# CH3-Isolation.net
KiCad netlist of a schematic drawn in Altium Designer
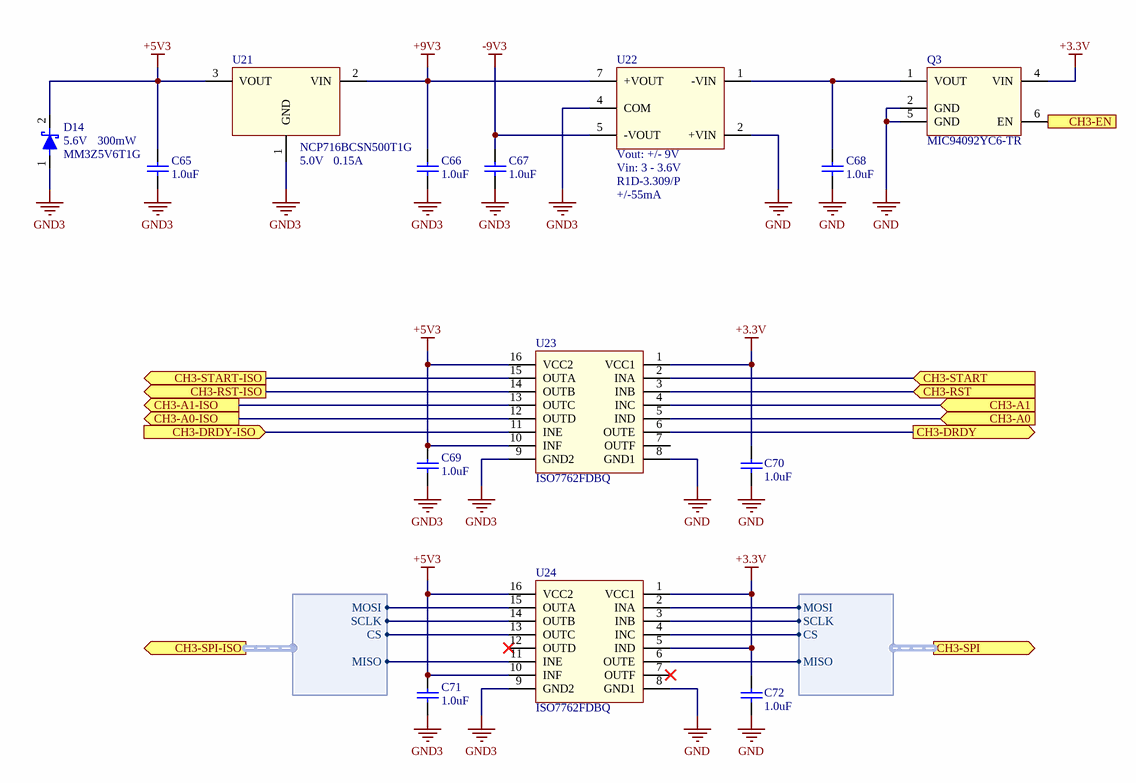
[diagram p0: CH3-Isolation.SchDoc]

(export (version "E")
  (design (tool "Eeschema 10.0.6"))
  (components
    (comp (ref "C65")
      (value "1.0uF")
      (footprint "CAP-0603")
      (description "CAP CER 1uF 25V X7R 0603")
      (fields (field (name "PARTNUMBER") "C0603C105M3RAC7867") (field (name "MANUFACTURER") "Kemet"))
      (libsource (lib "Kemet") (part "C0603C105M3RAC7867"))
    )
    (comp (ref "C66")
      (value "1.0uF")
      (footprint "CAP-0603")
      (description "CAP CER 1uF 25V X7R 0603")
      (fields (field (name "PARTNUMBER") "C0603C105M3RAC7867") (field (name "MANUFACTURER") "Kemet"))
      (libsource (lib "Kemet") (part "C0603C105M3RAC7867"))
    )
    (comp (ref "C67")
      (value "1.0uF")
      (footprint "CAP-0603")
      (description "CAP CER 1uF 25V X7R 0603")
      (fields (field (name "PARTNUMBER") "C0603C105M3RAC7867") (field (name "MANUFACTURER") "Kemet"))
      (libsource (lib "Kemet") (part "C0603C105M3RAC7867"))
    )
    (comp (ref "C68")
      (value "1.0uF")
      (footprint "CAP-0603")
      (description "CAP CER 1uF 25V X7R 0603")
      (fields (field (name "PARTNUMBER") "C0603C105M3RAC7867") (field (name "MANUFACTURER") "Kemet"))
      (libsource (lib "Kemet") (part "C0603C105M3RAC7867"))
    )
    (comp (ref "C69")
      (value "1.0uF")
      (footprint "CAP-0603")
      (description "CAP CER 1uF 25V X7R 0603")
      (fields (field (name "PARTNUMBER") "C0603C105M3RAC7867") (field (name "MANUFACTURER") "Kemet"))
      (libsource (lib "Kemet") (part "C0603C105M3RAC7867"))
    )
    (comp (ref "C70")
      (value "1.0uF")
      (footprint "CAP-0603")
      (description "CAP CER 1uF 25V X7R 0603")
      (fields (field (name "PARTNUMBER") "C0603C105M3RAC7867") (field (name "MANUFACTURER") "Kemet"))
      (libsource (lib "Kemet") (part "C0603C105M3RAC7867"))
    )
    (comp (ref "C71")
      (value "1.0uF")
      (footprint "CAP-0603")
      (description "CAP CER 1uF 25V X7R 0603")
      (fields (field (name "PARTNUMBER") "C0603C105M3RAC7867") (field (name "MANUFACTURER") "Kemet"))
      (libsource (lib "Kemet") (part "C0603C105M3RAC7867"))
    )
    (comp (ref "C72")
      (value "1.0uF")
      (footprint "CAP-0603")
      (description "CAP CER 1uF 25V X7R 0603")
      (fields (field (name "PARTNUMBER") "C0603C105M3RAC7867") (field (name "MANUFACTURER") "Kemet"))
      (libsource (lib "Kemet") (part "C0603C105M3RAC7867"))
    )
    (comp (ref "D14")
      (value "MM3Z5V6T1G")
      (footprint "SOD323 - DIODE UNIDIR")
      (description "Schottky Diode 30V 200mA SOT323")
      (fields
        (field (name "MANUFACTURER") "OnSemiconductor")
        (field (name "POWER") "300mW")
        (field (name "VZ") "5.6V")
        (field (name "PARTNUMBER") "MM3Z5V6T1G")
      )
      (libsource (lib "OnSemiconductors") (part "MM3Z5V6T1G"))
    )
    (comp (ref "Q3")
      (value "MIC94092YC6-TR")
      (footprint "TSSOP6")
      (fields (field (name "MANUFACTURER") "Microchip") (field (name "PARTNUMBER") "MIC94092YC6-TR"))
      (libsource (lib "Microchip") (part "MIC94092YC6-TR"))
    )
    (comp (ref "U21")
      (value "NCP716BCSN500T1G")
      (footprint "SOT23-5")
      (description "IC REG LDO 0.5V 0.15A TSOT23-5")
      (fields
        (field (name "MANUFACTURER") "ON Semiconductor")
        (field (name "PARTNUMBER") "NCP716BCSN500T1G")
        (field (name "VOLTAGE") "5.0V")
        (field (name "CURRENT") "0.15A")
      )
      (libsource (lib "OnSemiconductors") (part "NCP716BCSN500T1G"))
    )
    (comp (ref "U22")
      (value "R1D-3.309/P")
      (footprint "RECOM-R1D")
      (description "DC DC CONVERTER +/-9V 1W")
      (fields
        (field (name "MANUFACTURER") "Recom")
        (field (name "VOUT") "+/- 9V")
        (field (name "VIN") "3 - 3.6V")
        (field (name "PART NUMBER") "R1D-3.309/P")
        (field (name "CURRENT") "+/-55mA")
      )
      (libsource (lib "Recom") (part "R1D-3.309/P"))
    )
    (comp (ref "U23")
      (value "ISO7762FDBQ")
      (footprint "SSOP16")
      (description "Digital Isolator, six-channel, 4/2, 16-SSOP")
      (fields (field (name "MANUFACTURER") "Texas Instruments") (field (name "PARTNUMBER") "ISO7762FDBQ"))
      (libsource (lib "TexasInstruments") (part "ISO7762FDBQ"))
    )
    (comp (ref "U24")
      (value "ISO7762FDBQ")
      (footprint "SSOP16")
      (description "Digital Isolator, six-channel, 4/2, 16-SSOP")
      (fields (field (name "MANUFACTURER") "Texas Instruments") (field (name "PARTNUMBER") "ISO7762FDBQ"))
      (libsource (lib "TexasInstruments") (part "ISO7762FDBQ"))
    )
  )
  (nets
    (net (code "3") (name "+3.3V") (class "Default")
      (node (ref "C70") (pin "2") (pinfunction "2_2") (pintype "passive"))
      (node (ref "C72") (pin "2") (pinfunction "2_2") (pintype "passive"))
      (node (ref "Q3") (pin "4") (pinfunction "VIN_4") (pintype "passive"))
      (node (ref "U23") (pin "1") (pinfunction "VCC1_1") (pintype "passive"))
      (node (ref "U24") (pin "1") (pinfunction "VCC1_1") (pintype "passive"))
      (node (ref "U24") (pin "5") (pinfunction "IND_5") (pintype "passive"))
    )
    (net (code "4") (name "+5V3") (class "Default")
      (node (ref "C65") (pin "2") (pinfunction "2_2") (pintype "passive"))
      (node (ref "C69") (pin "2") (pinfunction "2_2") (pintype "passive"))
      (node (ref "C71") (pin "2") (pinfunction "2_2") (pintype "passive"))
      (node (ref "D14") (pin "2") (pinfunction "K_2") (pintype "passive"))
      (node (ref "U21") (pin "3") (pinfunction "VOUT_3") (pintype "passive"))
      (node (ref "U23") (pin "10") (pinfunction "INF_10") (pintype "passive"))
      (node (ref "U23") (pin "16") (pinfunction "VCC2_16") (pintype "passive"))
      (node (ref "U24") (pin "10") (pinfunction "INF_10") (pintype "passive"))
      (node (ref "U24") (pin "16") (pinfunction "VCC2_16") (pintype "passive"))
    )
    (net (code "5") (name "+9V3") (class "Default")
      (node (ref "C66") (pin "2") (pinfunction "2_2") (pintype "passive"))
      (node (ref "U21") (pin "2") (pinfunction "VIN_2") (pintype "passive"))
      (node (ref "U22") (pin "7") (pinfunction "+VOUT_7") (pintype "passive"))
    )
    (net (code "6") (name "-9V3") (class "Default")
      (node (ref "C67") (pin "2") (pinfunction "2_2") (pintype "passive"))
      (node (ref "U22") (pin "5") (pinfunction "-VOUT_5") (pintype "passive"))
    )
    (net (code "7") (name "/CH3-A0") (class "Default")
      (node (ref "U23") (pin "5") (pinfunction "IND_5") (pintype "passive"))
    )
    (net (code "8") (name "/CH3-A0-ISO") (class "Default")
      (node (ref "U23") (pin "12") (pinfunction "OUTD_12") (pintype "passive"))
    )
    (net (code "9") (name "/CH3-A1") (class "Default")
      (node (ref "U23") (pin "4") (pinfunction "INC_4") (pintype "passive"))
    )
    (net (code "10") (name "/CH3-A1-ISO") (class "Default")
      (node (ref "U23") (pin "13") (pinfunction "OUTC_13") (pintype "passive"))
    )
    (net (code "11") (name "/CH3-DRDY") (class "Default")
      (node (ref "U23") (pin "6") (pinfunction "OUTE_6") (pintype "passive"))
    )
    (net (code "12") (name "/CH3-DRDY-ISO") (class "Default")
      (node (ref "U23") (pin "11") (pinfunction "INE_11") (pintype "passive"))
    )
    (net (code "13") (name "/CH3-EN") (class "Default")
      (node (ref "Q3") (pin "6") (pinfunction "EN_6") (pintype "passive"))
    )
    (net (code "14") (name "/CH3-RST") (class "Default")
      (node (ref "U23") (pin "3") (pinfunction "INB_3") (pintype "passive"))
    )
    (net (code "15") (name "/CH3-RST-ISO") (class "Default")
      (node (ref "U23") (pin "14") (pinfunction "OUTB_14") (pintype "passive"))
    )
    (net (code "16") (name "/CH3-START") (class "Default")
      (node (ref "U23") (pin "2") (pinfunction "INA_2") (pintype "passive"))
    )
    (net (code "17") (name "/CH3-START-ISO") (class "Default")
      (node (ref "U23") (pin "15") (pinfunction "OUTA_15") (pintype "passive"))
    )
    (net (code "20") (name "GND") (class "Default")
      (node (ref "C68") (pin "1") (pinfunction "1_1") (pintype "passive"))
      (node (ref "C70") (pin "1") (pinfunction "1_1") (pintype "passive"))
      (node (ref "C72") (pin "1") (pinfunction "1_1") (pintype "passive"))
      (node (ref "Q3") (pin "2") (pinfunction "GND_2") (pintype "passive"))
      (node (ref "Q3") (pin "5") (pinfunction "GND_5") (pintype "passive"))
      (node (ref "U22") (pin "2") (pinfunction "+VIN_2") (pintype "passive"))
      (node (ref "U23") (pin "8") (pinfunction "GND1_8") (pintype "passive"))
      (node (ref "U24") (pin "8") (pinfunction "GND1_8") (pintype "passive"))
    )
    (net (code "21") (name "GND3") (class "Default")
      (node (ref "C65") (pin "1") (pinfunction "1_1") (pintype "passive"))
      (node (ref "C66") (pin "1") (pinfunction "1_1") (pintype "passive"))
      (node (ref "C67") (pin "1") (pinfunction "1_1") (pintype "passive"))
      (node (ref "C69") (pin "1") (pinfunction "1_1") (pintype "passive"))
      (node (ref "C71") (pin "1") (pinfunction "1_1") (pintype "passive"))
      (node (ref "D14") (pin "1") (pinfunction "A_1") (pintype "passive"))
      (node (ref "U21") (pin "1") (pinfunction "GND_1") (pintype "passive"))
      (node (ref "U22") (pin "4") (pinfunction "COM_4") (pintype "passive"))
      (node (ref "U23") (pin "9") (pinfunction "GND2_9") (pintype "passive"))
      (node (ref "U24") (pin "9") (pinfunction "GND2_9") (pintype "passive"))
    )
    (net (code "22") (name "Net-(Q3-VOUT)") (class "Default")
      (node (ref "C68") (pin "2") (pinfunction "2_2") (pintype "passive"))
      (node (ref "Q3") (pin "1") (pinfunction "VOUT_1") (pintype "passive"))
      (node (ref "U22") (pin "1") (pinfunction "-VIN_1") (pintype "passive"))
    )
    (net (code "23") (name "unconnected-(U23-OUTF-Pad7)") (class "Default")
      (node (ref "U23") (pin "7") (pinfunction "OUTF_7") (pintype "passive"))
    )
    (net (code "24") (name "unconnected-(U24-INA-Pad2)") (class "Default")
      (node (ref "U24") (pin "2") (pinfunction "INA_2") (pintype "passive"))
    )
    (net (code "25") (name "unconnected-(U24-INB-Pad3)") (class "Default")
      (node (ref "U24") (pin "3") (pinfunction "INB_3") (pintype "passive"))
    )
    (net (code "26") (name "unconnected-(U24-INC-Pad4)") (class "Default")
      (node (ref "U24") (pin "4") (pinfunction "INC_4") (pintype "passive"))
    )
    (net (code "27") (name "unconnected-(U24-INE-Pad11)") (class "Default")
      (node (ref "U24") (pin "11") (pinfunction "INE_11") (pintype "passive"))
    )
    (net (code "28") (name "unconnected-(U24-OUTA-Pad15)") (class "Default")
      (node (ref "U24") (pin "15") (pinfunction "OUTA_15") (pintype "passive"))
    )
    (net (code "29") (name "unconnected-(U24-OUTB-Pad14)") (class "Default")
      (node (ref "U24") (pin "14") (pinfunction "OUTB_14") (pintype "passive"))
    )
    (net (code "30") (name "unconnected-(U24-OUTC-Pad13)") (class "Default")
      (node (ref "U24") (pin "13") (pinfunction "OUTC_13") (pintype "passive"))
    )
    (net (code "31") (name "unconnected-(U24-OUTD-Pad12)") (class "Default")
      (node (ref "U24") (pin "12") (pinfunction "OUTD_12") (pintype "passive+no_connect"))
    )
    (net (code "32") (name "unconnected-(U24-OUTE-Pad6)") (class "Default")
      (node (ref "U24") (pin "6") (pinfunction "OUTE_6") (pintype "passive"))
    )
    (net (code "33") (name "unconnected-(U24-OUTF-Pad7)") (class "Default")
      (node (ref "U24") (pin "7") (pinfunction "OUTF_7") (pintype "passive+no_connect"))
    )
  )
)
